# electronic_igniter.net
KiCad netlist of a schematic drawn in EAGLE
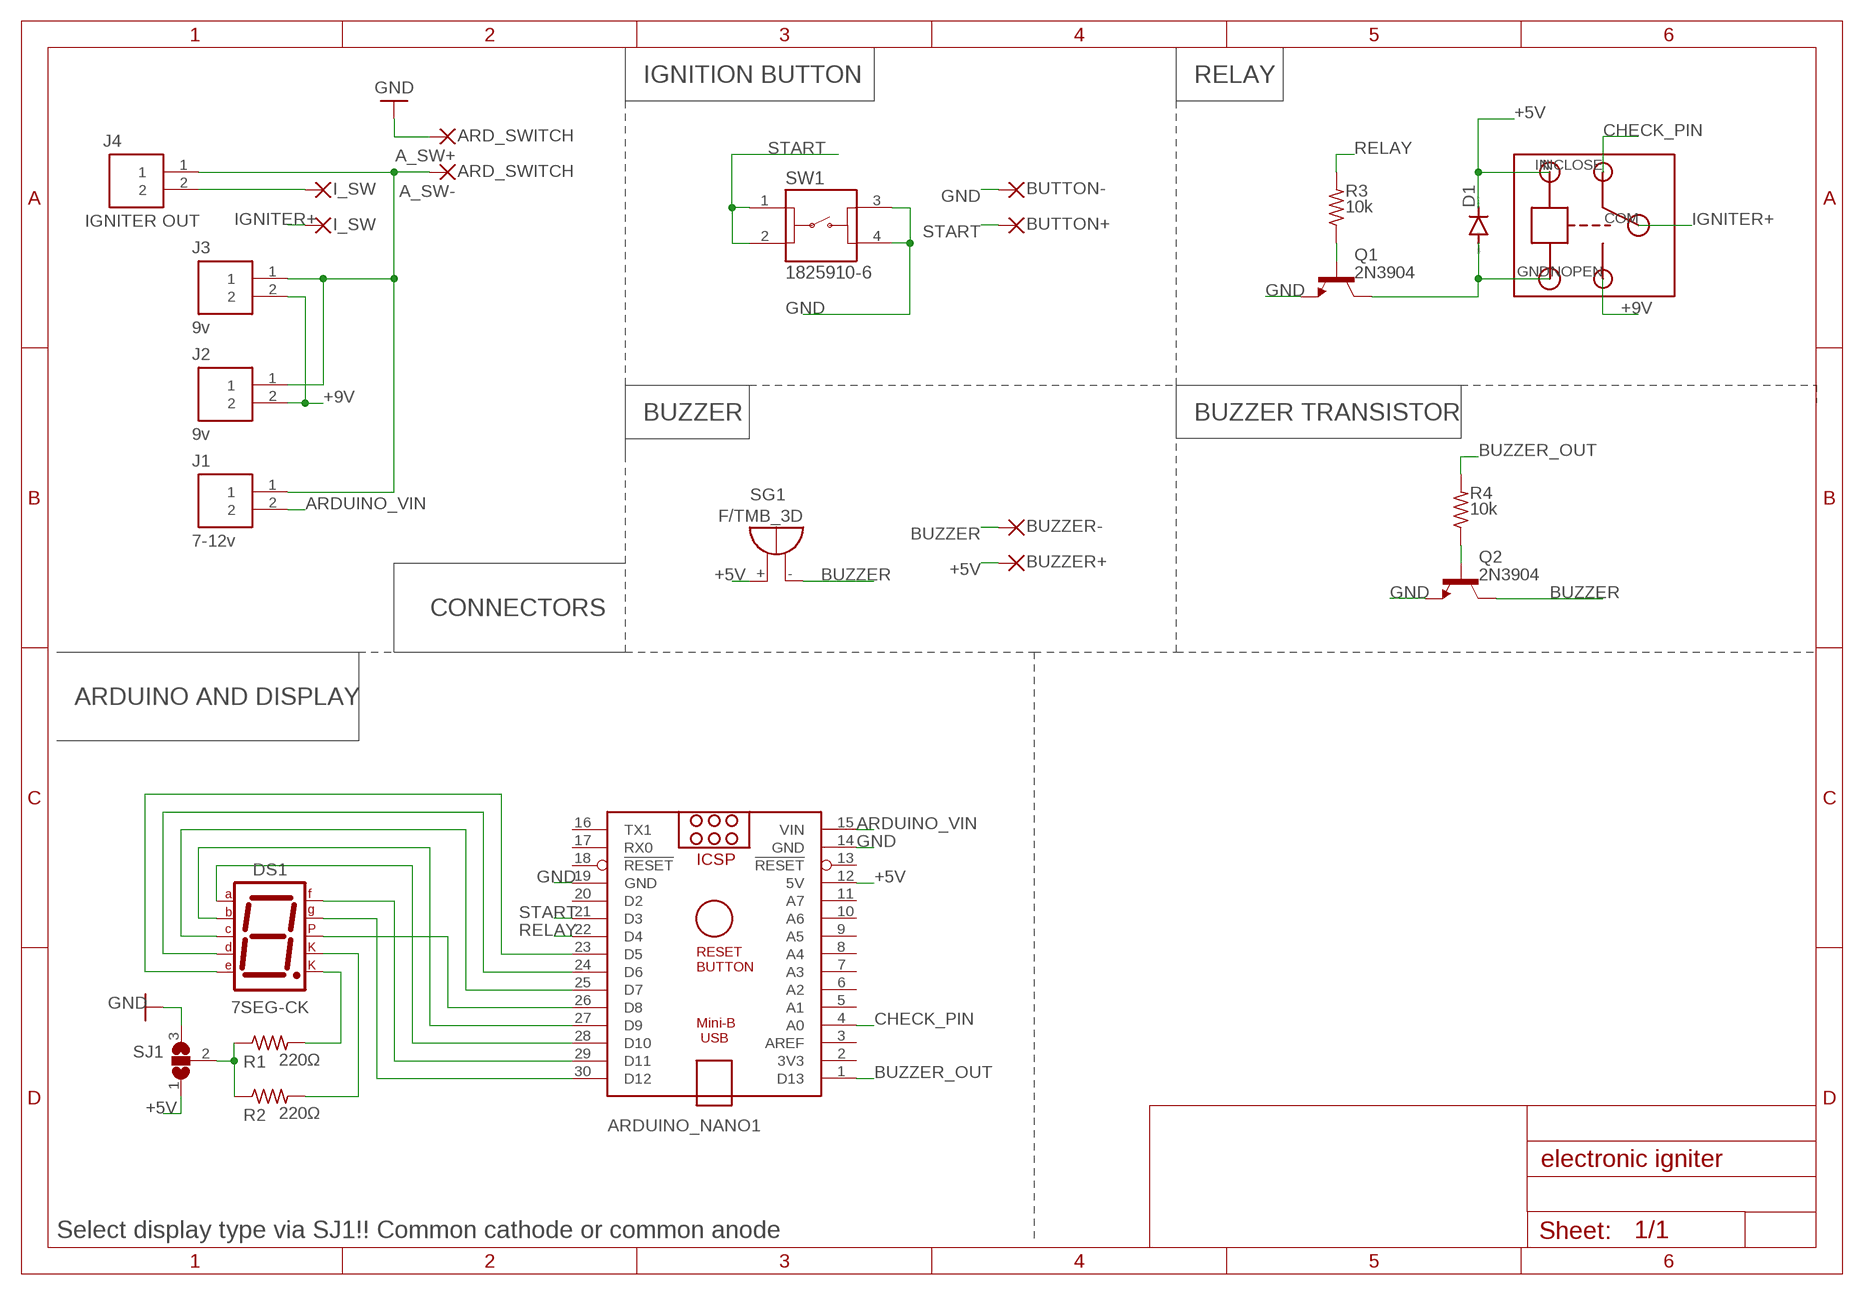
[diagram p0: schematic, sheet 1]

(export (version "E")
  (design (tool "Eeschema 10.0.6"))
  (components
    (comp (ref "ARDUINO_NANO1")
      (value "ARDUINO_NANO")
      (footprint "eagle-import:ARDUINO_NANO")
      (libsource (lib "eagle-import") (part "ARDUINO_NANO"))
    )
    (comp (ref "A_SW+")
      (value "ARD_SWITCH")
      (footprint "eagle-import:2,15_1,0")
      (libsource (lib "eagle-import") (part "2,15/1,0"))
    )
    (comp (ref "A_SW-")
      (value "ARD_SWITCH")
      (footprint "eagle-import:2,15_1,0")
      (libsource (lib "eagle-import") (part "2,15/1,0"))
    )
    (comp (ref "BUTTON+")
      (value "2,15/1,0")
      (footprint "eagle-import:2,15_1,0")
      (libsource (lib "eagle-import") (part "2,15/1,0"))
    )
    (comp (ref "BUTTON-")
      (value "2,15/1,0")
      (footprint "eagle-import:2,15_1,0")
      (libsource (lib "eagle-import") (part "2,15/1,0"))
    )
    (comp (ref "BUZZER+")
      (value "2,15/1,0")
      (footprint "eagle-import:2,15_1,0")
      (libsource (lib "eagle-import") (part "2,15/1,0"))
    )
    (comp (ref "BUZZER-")
      (value "2,15/1,0")
      (footprint "eagle-import:2,15_1,0")
      (libsource (lib "eagle-import") (part "2,15/1,0"))
    )
    (comp (ref "D1")
      (value "1N4148DO35-7")
      (footprint "eagle-import:DO35-7")
      (libsource (lib "eagle-import") (part "1N4148DO35-7"))
    )
    (comp (ref "DS1")
      (value "7SEG-CK")
      (footprint "eagle-import:7SEG-13")
      (libsource (lib "eagle-import") (part "7SEG-CK"))
    )
    (comp (ref "I_SW+")
      (value "I_SW")
      (footprint "eagle-import:2,15_1,0")
      (libsource (lib "eagle-import") (part "2,15/1,0"))
    )
    (comp (ref "I_SW-")
      (value "I_SW")
      (footprint "eagle-import:2,15_1,0")
      (libsource (lib "eagle-import") (part "2,15/1,0"))
    )
    (comp (ref "J1")
      (value "7-12v")
      (footprint "eagle-import:1803277")
      (fields
        (field (name "DIGI_KEY_PART_NUMBER") "277-1206-ND")
        (field (name "MANUFACTURER") "Phoenix Contact")
        (field (name "MPN") "1803277")
        (field (name "CREATED_BY") "PCBLayout.com")
      )
      (libsource (lib "eagle-import") (part "1803277"))
    )
    (comp (ref "J2")
      (value "9v")
      (footprint "eagle-import:1803277")
      (fields
        (field (name "DIGI_KEY_PART_NUMBER") "277-1206-ND")
        (field (name "MANUFACTURER") "Phoenix Contact")
        (field (name "MPN") "1803277")
        (field (name "CREATED_BY") "PCBLayout.com")
      )
      (libsource (lib "eagle-import") (part "1803277"))
    )
    (comp (ref "J3")
      (value "9v")
      (footprint "eagle-import:1803277")
      (fields
        (field (name "DIGI_KEY_PART_NUMBER") "277-1206-ND")
        (field (name "MANUFACTURER") "Phoenix Contact")
        (field (name "MPN") "1803277")
        (field (name "CREATED_BY") "PCBLayout.com")
      )
      (libsource (lib "eagle-import") (part "1803277"))
    )
    (comp (ref "J4")
      (value "IGNITER OUT")
      (footprint "eagle-import:1803277")
      (fields
        (field (name "DIGI_KEY_PART_NUMBER") "277-1206-ND")
        (field (name "MANUFACTURER") "Phoenix Contact")
        (field (name "MPN") "1803277")
        (field (name "CREATED_BY") "PCBLayout.com")
      )
      (libsource (lib "eagle-import") (part "1803277"))
    )
    (comp (ref "Q1")
      (value "2N3904")
      (footprint "eagle-import:TO92")
      (libsource (lib "eagle-import") (part "2N3904"))
    )
    (comp (ref "Q2")
      (value "2N3904")
      (footprint "eagle-import:TO92")
      (libsource (lib "eagle-import") (part "2N3904"))
    )
    (comp (ref "R1")
      (value "220Ω")
      (footprint "eagle-import:0204_7")
      (libsource (lib "eagle-import") (part "R-US_0204/7"))
    )
    (comp (ref "R2")
      (value "220Ω")
      (footprint "eagle-import:0204_7")
      (libsource (lib "eagle-import") (part "R-US_0204/7"))
    )
    (comp (ref "R3")
      (value "10k")
      (footprint "eagle-import:0204_7")
      (libsource (lib "eagle-import") (part "R-US_0204/7"))
    )
    (comp (ref "R4")
      (value "10k")
      (footprint "eagle-import:0204_7")
      (libsource (lib "eagle-import") (part "R-US_0204/7"))
    )
    (comp (ref "SG1")
      (value "F/TMB_3D")
      (footprint "eagle-import:F_TMB")
      (libsource (lib "eagle-import") (part "F/TMB_3D"))
    )
    (comp (ref "SJ1")
      (value "SJ2WW")
      (footprint "eagle-import:SJ_2W")
      (libsource (lib "eagle-import") (part "SJ2WW"))
    )
    (comp (ref "SW1")
      (value "1825910-6")
      (footprint "eagle-import:1825910-6")
      (fields
        (field (name "DIGIKEY_PART_NUMBER") "450-1650-ND")
        (field (name "MANUFACTURER") "TE Connectivity ALCOSWITCH Switches")
        (field (name "CREATED_BY") " PCBLayout.com")
      )
      (libsource (lib "eagle-import") (part "1825910-6"))
    )
    (comp (ref "U$1")
      (value "T73")
      (footprint "eagle-import:RELAY")
      (libsource (lib "eagle-import") (part "T73"))
    )
  )
  (nets
    (net (code "1") (name "/+5V") (class "Default")
      (node (ref "ARDUINO_NANO1") (pin "12") (pinfunction "5V_12") (pintype "power_in"))
      (node (ref "BUZZER+") (pin "1") (pinfunction "P_1") (pintype "passive"))
      (node (ref "D1") (pin "C") (pinfunction "C_C") (pintype "passive"))
      (node (ref "SG1") (pin "+") (pinfunction "+_+") (pintype "passive"))
      (node (ref "SJ1") (pin "1") (pinfunction "1_1") (pintype "passive"))
      (node (ref "U$1") (pin "IN") (pinfunction "IN_IN") (pintype "bidirectional"))
    )
    (net (code "2") (name "/+9V") (class "Default")
      (node (ref "J2") (pin "2") (pinfunction "2_2") (pintype "passive"))
      (node (ref "J3") (pin "2") (pinfunction "2_2") (pintype "passive"))
      (node (ref "U$1") (pin "NOPEN") (pinfunction "NOPEN_NOPEN") (pintype "bidirectional"))
    )
    (net (code "3") (name "/ARDUINO_VIN") (class "Default")
      (node (ref "ARDUINO_NANO1") (pin "15") (pinfunction "VIN_15") (pintype "power_in"))
      (node (ref "J1") (pin "2") (pinfunction "2_2") (pintype "passive"))
    )
    (net (code "4") (name "/BUZZER") (class "Default")
      (node (ref "BUZZER-") (pin "1") (pinfunction "P_1") (pintype "passive"))
      (node (ref "Q2") (pin "1") (pinfunction "C_1") (pintype "passive"))
      (node (ref "SG1") (pin "-") (pinfunction "-_-") (pintype "passive"))
    )
    (net (code "5") (name "/BUZZER_OUT") (class "Default")
      (node (ref "ARDUINO_NANO1") (pin "1") (pinfunction "D13_1") (pintype "bidirectional"))
      (node (ref "R4") (pin "2") (pinfunction "2_2") (pintype "passive"))
    )
    (net (code "6") (name "/CHECK_PIN") (class "Default")
      (node (ref "ARDUINO_NANO1") (pin "4") (pinfunction "A0_4") (pintype "bidirectional"))
      (node (ref "U$1") (pin "NCLOSE") (pinfunction "NCLOSE_NCLOSE") (pintype "bidirectional"))
    )
    (net (code "7") (name "/IGNITER+") (class "Default")
      (node (ref "I_SW+") (pin "1") (pinfunction "P_1") (pintype "passive"))
      (node (ref "U$1") (pin "COM") (pinfunction "COM_COM") (pintype "bidirectional"))
    )
    (net (code "8") (name "/RELAY") (class "Default")
      (node (ref "ARDUINO_NANO1") (pin "22") (pinfunction "D4_22") (pintype "bidirectional"))
      (node (ref "R3") (pin "2") (pinfunction "2_2") (pintype "passive"))
    )
    (net (code "9") (name "/START") (class "Default")
      (node (ref "ARDUINO_NANO1") (pin "21") (pinfunction "D3_21") (pintype "bidirectional"))
      (node (ref "BUTTON+") (pin "1") (pinfunction "P_1") (pintype "passive"))
      (node (ref "SW1") (pin "1") (pinfunction "1_1") (pintype "passive"))
      (node (ref "SW1") (pin "2") (pinfunction "2_2") (pintype "passive"))
    )
    (net (code "10") (name "GND") (class "Default")
      (node (ref "ARDUINO_NANO1") (pin "14") (pinfunction "GND_14") (pintype "power_in"))
      (node (ref "ARDUINO_NANO1") (pin "19") (pinfunction "GND_19") (pintype "power_in"))
      (node (ref "A_SW+") (pin "1") (pinfunction "P_1") (pintype "passive"))
      (node (ref "BUTTON-") (pin "1") (pinfunction "P_1") (pintype "passive"))
      (node (ref "Q1") (pin "3") (pinfunction "E_3") (pintype "passive"))
      (node (ref "Q2") (pin "3") (pinfunction "E_3") (pintype "passive"))
      (node (ref "SJ1") (pin "3") (pinfunction "3_3") (pintype "passive"))
      (node (ref "SW1") (pin "3") (pinfunction "3_3") (pintype "passive"))
      (node (ref "SW1") (pin "4") (pinfunction "4_4") (pintype "passive"))
    )
    (net (code "11") (name "Net-(ARDUINO_NANO1-D5)") (class "Default")
      (node (ref "ARDUINO_NANO1") (pin "23") (pinfunction "D5_23") (pintype "bidirectional"))
      (node (ref "DS1") (pin "1") (pinfunction "E_1") (pintype "passive"))
    )
    (net (code "12") (name "Net-(ARDUINO_NANO1-D6)") (class "Default")
      (node (ref "ARDUINO_NANO1") (pin "24") (pinfunction "D6_24") (pintype "bidirectional"))
      (node (ref "DS1") (pin "2") (pinfunction "D_2") (pintype "passive"))
    )
    (net (code "13") (name "Net-(ARDUINO_NANO1-D7)") (class "Default")
      (node (ref "ARDUINO_NANO1") (pin "25") (pinfunction "D7_25") (pintype "bidirectional"))
      (node (ref "DS1") (pin "4") (pinfunction "C_4") (pintype "passive"))
    )
    (net (code "14") (name "Net-(ARDUINO_NANO1-D8)") (class "Default")
      (node (ref "ARDUINO_NANO1") (pin "26") (pinfunction "D8_26") (pintype "bidirectional"))
      (node (ref "DS1") (pin "5") (pinfunction "DP_5") (pintype "passive"))
    )
    (net (code "15") (name "Net-(ARDUINO_NANO1-D9)") (class "Default")
      (node (ref "ARDUINO_NANO1") (pin "27") (pinfunction "D9_27") (pintype "bidirectional"))
      (node (ref "DS1") (pin "6") (pinfunction "B_6") (pintype "passive"))
    )
    (net (code "16") (name "Net-(ARDUINO_NANO1-D10)") (class "Default")
      (node (ref "ARDUINO_NANO1") (pin "28") (pinfunction "D10_28") (pintype "bidirectional"))
      (node (ref "DS1") (pin "7") (pinfunction "A_7") (pintype "passive"))
    )
    (net (code "17") (name "Net-(ARDUINO_NANO1-D11)") (class "Default")
      (node (ref "ARDUINO_NANO1") (pin "29") (pinfunction "D11_29") (pintype "bidirectional"))
      (node (ref "DS1") (pin "9") (pinfunction "F_9") (pintype "passive"))
    )
    (net (code "18") (name "Net-(ARDUINO_NANO1-D12)") (class "Default")
      (node (ref "ARDUINO_NANO1") (pin "30") (pinfunction "D12_30") (pintype "bidirectional"))
      (node (ref "DS1") (pin "10") (pinfunction "G_10") (pintype "passive"))
    )
    (net (code "19") (name "Net-(A_SW--P)") (class "Default")
      (node (ref "A_SW-") (pin "1") (pinfunction "P_1") (pintype "passive"))
      (node (ref "J1") (pin "1") (pinfunction "1_1") (pintype "passive"))
      (node (ref "J2") (pin "1") (pinfunction "1_1") (pintype "passive"))
      (node (ref "J3") (pin "1") (pinfunction "1_1") (pintype "passive"))
      (node (ref "J4") (pin "1") (pinfunction "1_1") (pintype "passive"))
    )
    (net (code "20") (name "Net-(DS1-CK1)") (class "Default")
      (node (ref "DS1") (pin "3") (pinfunction "CK1_3") (pintype "passive"))
      (node (ref "R2") (pin "2") (pinfunction "2_2") (pintype "passive"))
    )
    (net (code "21") (name "Net-(DS1-CK2)") (class "Default")
      (node (ref "DS1") (pin "8") (pinfunction "CK2_8") (pintype "passive"))
      (node (ref "R1") (pin "2") (pinfunction "2_2") (pintype "passive"))
    )
    (net (code "22") (name "Net-(I_SW--P)") (class "Default")
      (node (ref "I_SW-") (pin "1") (pinfunction "P_1") (pintype "passive"))
      (node (ref "J4") (pin "2") (pinfunction "2_2") (pintype "passive"))
    )
    (net (code "23") (name "Net-(Q1-B)") (class "Default")
      (node (ref "Q1") (pin "2") (pinfunction "B_2") (pintype "passive"))
      (node (ref "R3") (pin "1") (pinfunction "1_1") (pintype "passive"))
    )
    (net (code "24") (name "Net-(Q1-C)") (class "Default")
      (node (ref "D1") (pin "A") (pinfunction "A_A") (pintype "passive"))
      (node (ref "Q1") (pin "1") (pinfunction "C_1") (pintype "passive"))
      (node (ref "U$1") (pin "GND") (pinfunction "GND_GND") (pintype "bidirectional"))
    )
    (net (code "25") (name "Net-(Q2-B)") (class "Default")
      (node (ref "Q2") (pin "2") (pinfunction "B_2") (pintype "passive"))
      (node (ref "R4") (pin "1") (pinfunction "1_1") (pintype "passive"))
    )
    (net (code "26") (name "Net-(R1-Pad1)") (class "Default")
      (node (ref "R1") (pin "1") (pinfunction "1_1") (pintype "passive"))
      (node (ref "R2") (pin "1") (pinfunction "1_1") (pintype "passive"))
      (node (ref "SJ1") (pin "2") (pinfunction "2_2") (pintype "passive"))
    )
    (net (code "27") (name "unconnected-(ARDUINO_NANO1-3V3-Pad2)") (class "Default")
      (node (ref "ARDUINO_NANO1") (pin "2") (pinfunction "3V3_2") (pintype "output"))
    )
    (net (code "28") (name "unconnected-(ARDUINO_NANO1-A1-Pad5)") (class "Default")
      (node (ref "ARDUINO_NANO1") (pin "5") (pinfunction "A1_5") (pintype "bidirectional"))
    )
    (net (code "29") (name "unconnected-(ARDUINO_NANO1-A2-Pad6)") (class "Default")
      (node (ref "ARDUINO_NANO1") (pin "6") (pinfunction "A2_6") (pintype "bidirectional"))
    )
    (net (code "30") (name "unconnected-(ARDUINO_NANO1-A3-Pad7)") (class "Default")
      (node (ref "ARDUINO_NANO1") (pin "7") (pinfunction "A3_7") (pintype "bidirectional"))
    )
    (net (code "31") (name "unconnected-(ARDUINO_NANO1-A4-Pad8)") (class "Default")
      (node (ref "ARDUINO_NANO1") (pin "8") (pinfunction "A4_8") (pintype "bidirectional"))
    )
    (net (code "32") (name "unconnected-(ARDUINO_NANO1-A5-Pad9)") (class "Default")
      (node (ref "ARDUINO_NANO1") (pin "9") (pinfunction "A5_9") (pintype "bidirectional"))
    )
    (net (code "33") (name "unconnected-(ARDUINO_NANO1-A6-Pad10)") (class "Default")
      (node (ref "ARDUINO_NANO1") (pin "10") (pinfunction "A6_10") (pintype "bidirectional"))
    )
    (net (code "34") (name "unconnected-(ARDUINO_NANO1-A7-Pad11)") (class "Default")
      (node (ref "ARDUINO_NANO1") (pin "11") (pinfunction "A7_11") (pintype "bidirectional"))
    )
    (net (code "35") (name "unconnected-(ARDUINO_NANO1-AREF-Pad3)") (class "Default")
      (node (ref "ARDUINO_NANO1") (pin "3") (pinfunction "AREF_3") (pintype "input"))
    )
    (net (code "36") (name "unconnected-(ARDUINO_NANO1-D2-Pad20)") (class "Default")
      (node (ref "ARDUINO_NANO1") (pin "20") (pinfunction "D2_20") (pintype "bidirectional"))
    )
    (net (code "37") (name "unconnected-(ARDUINO_NANO1-RX0-Pad17)") (class "Default")
      (node (ref "ARDUINO_NANO1") (pin "17") (pinfunction "RX0_17") (pintype "bidirectional"))
    )
    (net (code "38") (name "unconnected-(ARDUINO_NANO1-TX1-Pad16)") (class "Default")
      (node (ref "ARDUINO_NANO1") (pin "16") (pinfunction "TX1_16") (pintype "bidirectional"))
    )
    (net (code "39") (name "unconnected-(ARDUINO_NANO1-~{RESET}-Pad13)") (class "Default")
      (node (ref "ARDUINO_NANO1") (pin "13") (pinfunction "~{RESET}_13") (pintype "input"))
    )
    (net (code "40") (name "unconnected-(ARDUINO_NANO1-~{RESET}-Pad18)") (class "Default")
      (node (ref "ARDUINO_NANO1") (pin "18") (pinfunction "~{RESET}_18") (pintype "input"))
    )
  )
)
